# Adapter_V1_0.net
KiCad netlist of a schematic drawn in EAGLE
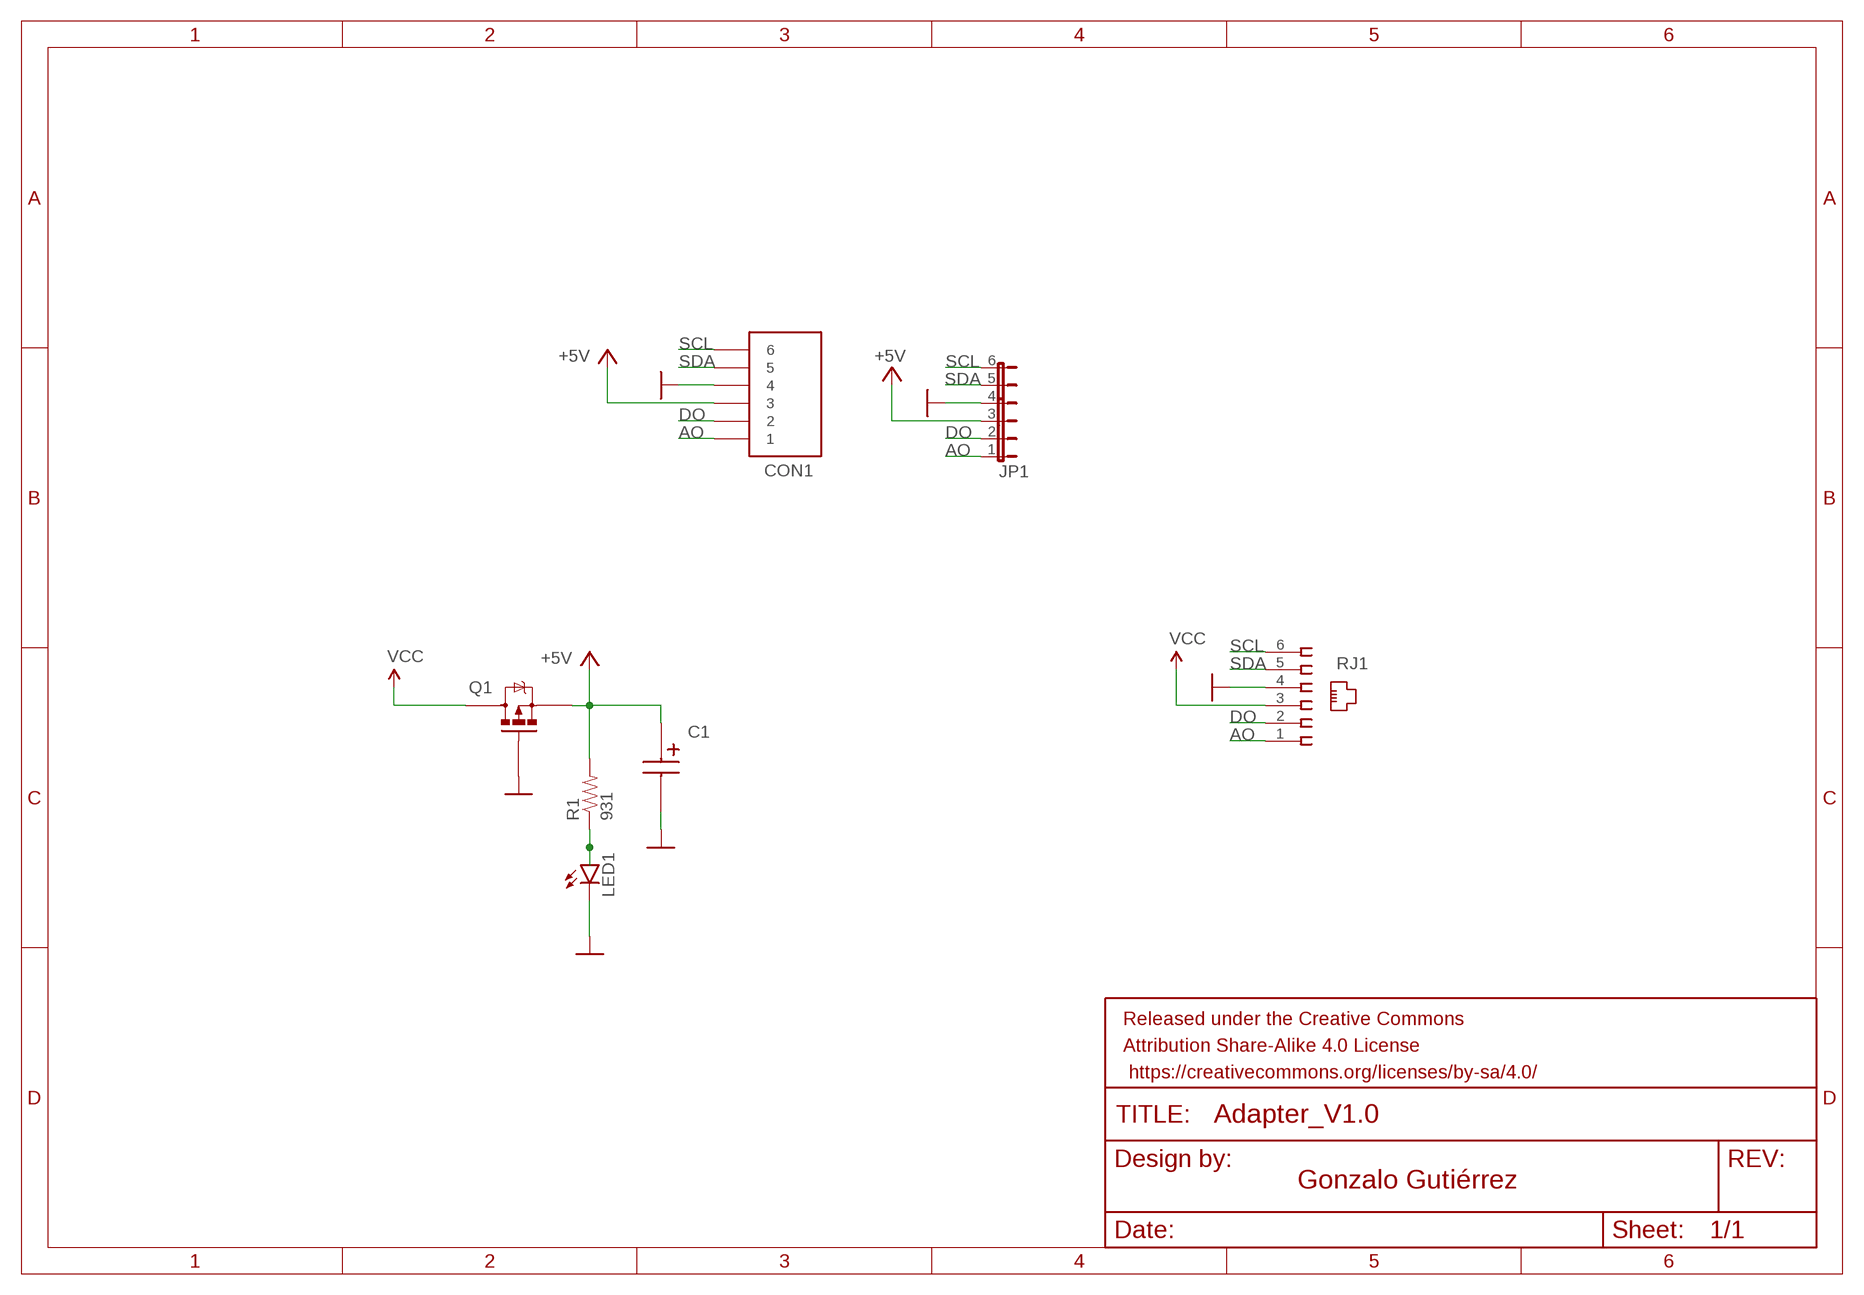
[diagram p0: schematic, sheet 1]

(export (version "E")
  (design (tool "Eeschema 10.0.6"))
  (components
    (comp (ref "C1")
      (value "220uF")
      (footprint "eagle-import:CAPPRD200W80D500H1100")
      (fields (field (name "MANUFACTURER_PART_NUMBER") "860010372006") (field (name "MPN") "227CKS010M"))
      (libsource (lib "eagle-import") (part "860010372006"))
    )
    (comp (ref "CON1")
      (value "1990041KF250A-2.5-6P")
      (footprint "eagle-import:KF250A-2.5-6P")
      (fields (field (name "MPN") "1990041"))
      (libsource (lib "eagle-import") (part "1990041KF250A-2.5-6P"))
    )
    (comp (ref "JP1")
      (value "JP6E")
      (footprint "eagle-import:JP6")
      (libsource (lib "eagle-import") (part "JP6E"))
    )
    (comp (ref "LED1")
      (value "LED0603")
      (footprint "eagle-import:LED-0603")
      (fields (field (name "MPN") "LTST-C193KRKT-5A "))
      (libsource (lib "eagle-import") (part "LED0603"))
    )
    (comp (ref "Q1")
      (value "IRLML2244TRPBF")
      (footprint "eagle-import:SOT95P237X112-3N")
      (description "HEXFET Power MOSFET")
      (fields
        (field (name "ARROW_PART_NUMBER") "IRLML2244TRPBF")
        (field (name "HEIGHT") "mm")
        (field (name "MANUFACTURER_NAME") "International Rectifier")
        (field (name "MANUFACTURER_PART_NUMBER") "IRLML2244TRPBF")
      )
      (libsource (lib "eagle-import") (part "IRLML2244TRPBF"))
    )
    (comp (ref "R1")
      (value "931")
      (footprint "eagle-import:RESC1005X35")
      (fields (field (name "MPN") "RC0402FR-07931RL"))
      (libsource (lib "eagle-import") (part "RES_0402"))
    )
    (comp (ref "RJ1")
      (value "615006138421")
      (footprint "eagle-import:615006138421")
      (fields (field (name "RS_PART_NUMBER") "7350282"))
      (libsource (lib "eagle-import") (part "615006138421"))
    )
  )
  (nets
    (net (code "1") (name "+5V") (class "Default")
      (node (ref "C1") (pin "1") (pinfunction "+_1") (pintype "bidirectional"))
      (node (ref "CON1") (pin "3") (pinfunction "3_3") (pintype "bidirectional"))
      (node (ref "JP1") (pin "3") (pinfunction "3_3") (pintype "passive"))
      (node (ref "Q1") (pin "2") (pinfunction "S_2") (pintype "bidirectional"))
      (node (ref "R1") (pin "2") (pinfunction "2_2") (pintype "passive"))
    )
    (net (code "2") (name "/AO") (class "Default")
      (node (ref "CON1") (pin "1") (pinfunction "1_1") (pintype "bidirectional"))
      (node (ref "JP1") (pin "1") (pinfunction "1_1") (pintype "passive"))
      (node (ref "RJ1") (pin "1") (pinfunction "1_1") (pintype "input"))
    )
    (net (code "3") (name "/DO") (class "Default")
      (node (ref "CON1") (pin "2") (pinfunction "2_2") (pintype "bidirectional"))
      (node (ref "JP1") (pin "2") (pinfunction "2_2") (pintype "passive"))
      (node (ref "RJ1") (pin "2") (pinfunction "2_2") (pintype "input"))
    )
    (net (code "4") (name "/SCL") (class "Default")
      (node (ref "CON1") (pin "6") (pinfunction "6_6") (pintype "bidirectional"))
      (node (ref "JP1") (pin "6") (pinfunction "6_6") (pintype "passive"))
      (node (ref "RJ1") (pin "6") (pinfunction "6_6") (pintype "input"))
    )
    (net (code "5") (name "/SDA") (class "Default")
      (node (ref "CON1") (pin "5") (pinfunction "5_5") (pintype "bidirectional"))
      (node (ref "JP1") (pin "5") (pinfunction "5_5") (pintype "passive"))
      (node (ref "RJ1") (pin "5") (pinfunction "5_5") (pintype "input"))
    )
    (net (code "6") (name "GND") (class "Default")
      (node (ref "C1") (pin "2") (pinfunction "-_2") (pintype "bidirectional"))
      (node (ref "CON1") (pin "4") (pinfunction "4_4") (pintype "bidirectional"))
      (node (ref "JP1") (pin "4") (pinfunction "4_4") (pintype "passive"))
      (node (ref "LED1") (pin "C") (pinfunction "C_C") (pintype "passive"))
      (node (ref "Q1") (pin "1") (pinfunction "G_1") (pintype "bidirectional"))
      (node (ref "RJ1") (pin "4") (pinfunction "4_4") (pintype "input"))
    )
    (net (code "7") (name "Net-(LED1-PadA)") (class "Default")
      (node (ref "LED1") (pin "A") (pinfunction "A_A") (pintype "passive"))
      (node (ref "R1") (pin "1") (pinfunction "1_1") (pintype "passive"))
    )
    (net (code "8") (name "VCC") (class "Default")
      (node (ref "Q1") (pin "3") (pinfunction "D_3") (pintype "bidirectional"))
      (node (ref "RJ1") (pin "3") (pinfunction "3_3") (pintype "input"))
    )
  )
)
